# Photodiode_TIA.net
KiCad netlist of a schematic drawn in Altium Designer
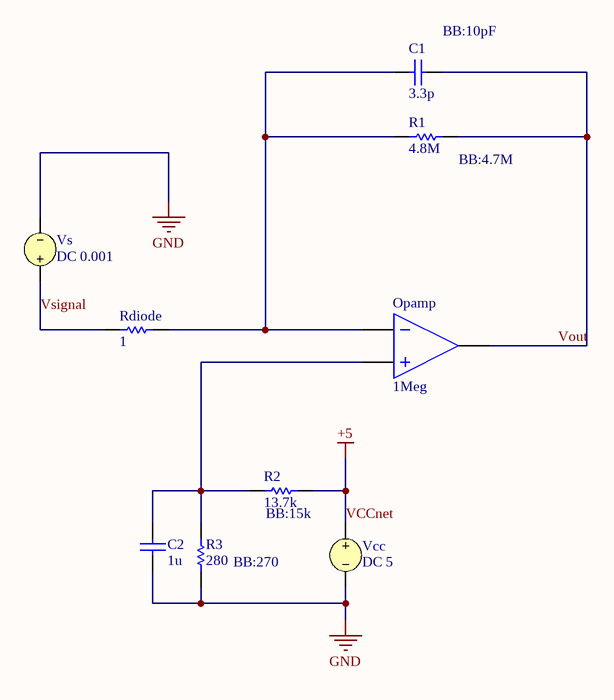
[diagram p0: Photodiode TIA.SchDoc]

(export (version "E")
  (design (tool "Eeschema 10.0.6"))
  (components
    (comp (ref "C1")
      (value "3.3p")
      (description "Capacitor")
      (libsource (lib "Simulation Generic Components") (part "Capacitor"))
    )
    (comp (ref "C2")
      (value "1u")
      (description "Capacitor")
      (libsource (lib "Simulation Generic Components") (part "Capacitor"))
    )
    (comp (ref "Opamp")
      (value "Ideal Operational Amplifier")
      (fields (field (name "GAIN") "1Meg"))
      (libsource (lib "Simulation Generic Components") (part "OpAmp"))
    )
    (comp (ref "R1")
      (value "4.8M")
      (description "Resistor")
      (libsource (lib "Simulation Generic Components") (part "Resistor"))
    )
    (comp (ref "R2")
      (value "13.7k")
      (description "Resistor")
      (libsource (lib "Simulation Generic Components") (part "Resistor"))
    )
    (comp (ref "R3")
      (value "280")
      (description "Resistor")
      (libsource (lib "Simulation Generic Components") (part "Resistor"))
    )
    (comp (ref "Rdiode")
      (value "1")
      (description "Resistor")
      (libsource (lib "Simulation Generic Components") (part "Resistor"))
    )
    (comp (ref "Vcc")
      (value "DC 5")
      (description "Voltage Source")
      (fields (field (name "PUBLISHER") "Altium Limited"))
      (libsource (lib "Simulation Generic Components") (part "VSRC"))
    )
    (comp (ref "Vs")
      (value "DC 0.001")
      (description "Voltage Source")
      (fields (field (name "PUBLISHER") "Altium Limited"))
      (libsource (lib "Simulation Generic Components") (part "VSRC"))
    )
  )
  (nets
    (net (code "1") (name "+5") (class "Default")
      (node (ref "R2") (pin "1") (pinfunction "1_1") (pintype "passive"))
      (node (ref "Vcc") (pin "1") (pinfunction "1_1") (pintype "passive"))
    )
    (net (code "2") (name "/Vout") (class "Default")
      (node (ref "C1") (pin "1") (pinfunction "1_1") (pintype "passive"))
      (node (ref "Opamp") (pin "3") (pinfunction "OUT_3") (pintype "passive"))
      (node (ref "R1") (pin "1") (pinfunction "1_1") (pintype "passive"))
    )
    (net (code "3") (name "/Vsignal") (class "Default")
      (node (ref "Rdiode") (pin "2") (pinfunction "2_2") (pintype "passive"))
      (node (ref "Vs") (pin "1") (pinfunction "1_1") (pintype "passive"))
    )
    (net (code "4") (name "GND") (class "Default")
      (node (ref "C2") (pin "1") (pinfunction "1_1") (pintype "passive"))
      (node (ref "R3") (pin "1") (pinfunction "1_1") (pintype "passive"))
      (node (ref "Vcc") (pin "2") (pinfunction "2_2") (pintype "passive"))
      (node (ref "Vs") (pin "2") (pinfunction "2_2") (pintype "passive"))
    )
    (net (code "5") (name "Net-(Opamp-IN+)") (class "Default")
      (node (ref "C2") (pin "2") (pinfunction "2_2") (pintype "passive"))
      (node (ref "Opamp") (pin "2") (pinfunction "IN+_2") (pintype "passive"))
      (node (ref "R2") (pin "2") (pinfunction "2_2") (pintype "passive"))
      (node (ref "R3") (pin "2") (pinfunction "2_2") (pintype "passive"))
    )
    (net (code "6") (name "Net-(Opamp-IN-)") (class "Default")
      (node (ref "C1") (pin "2") (pinfunction "2_2") (pintype "passive"))
      (node (ref "Opamp") (pin "1") (pinfunction "IN-_1") (pintype "passive"))
      (node (ref "R1") (pin "2") (pinfunction "2_2") (pintype "passive"))
      (node (ref "Rdiode") (pin "1") (pinfunction "1_1") (pintype "passive"))
    )
  )
)
